# Ups_chg.net
KiCad netlist of a schematic drawn in Altium Designer
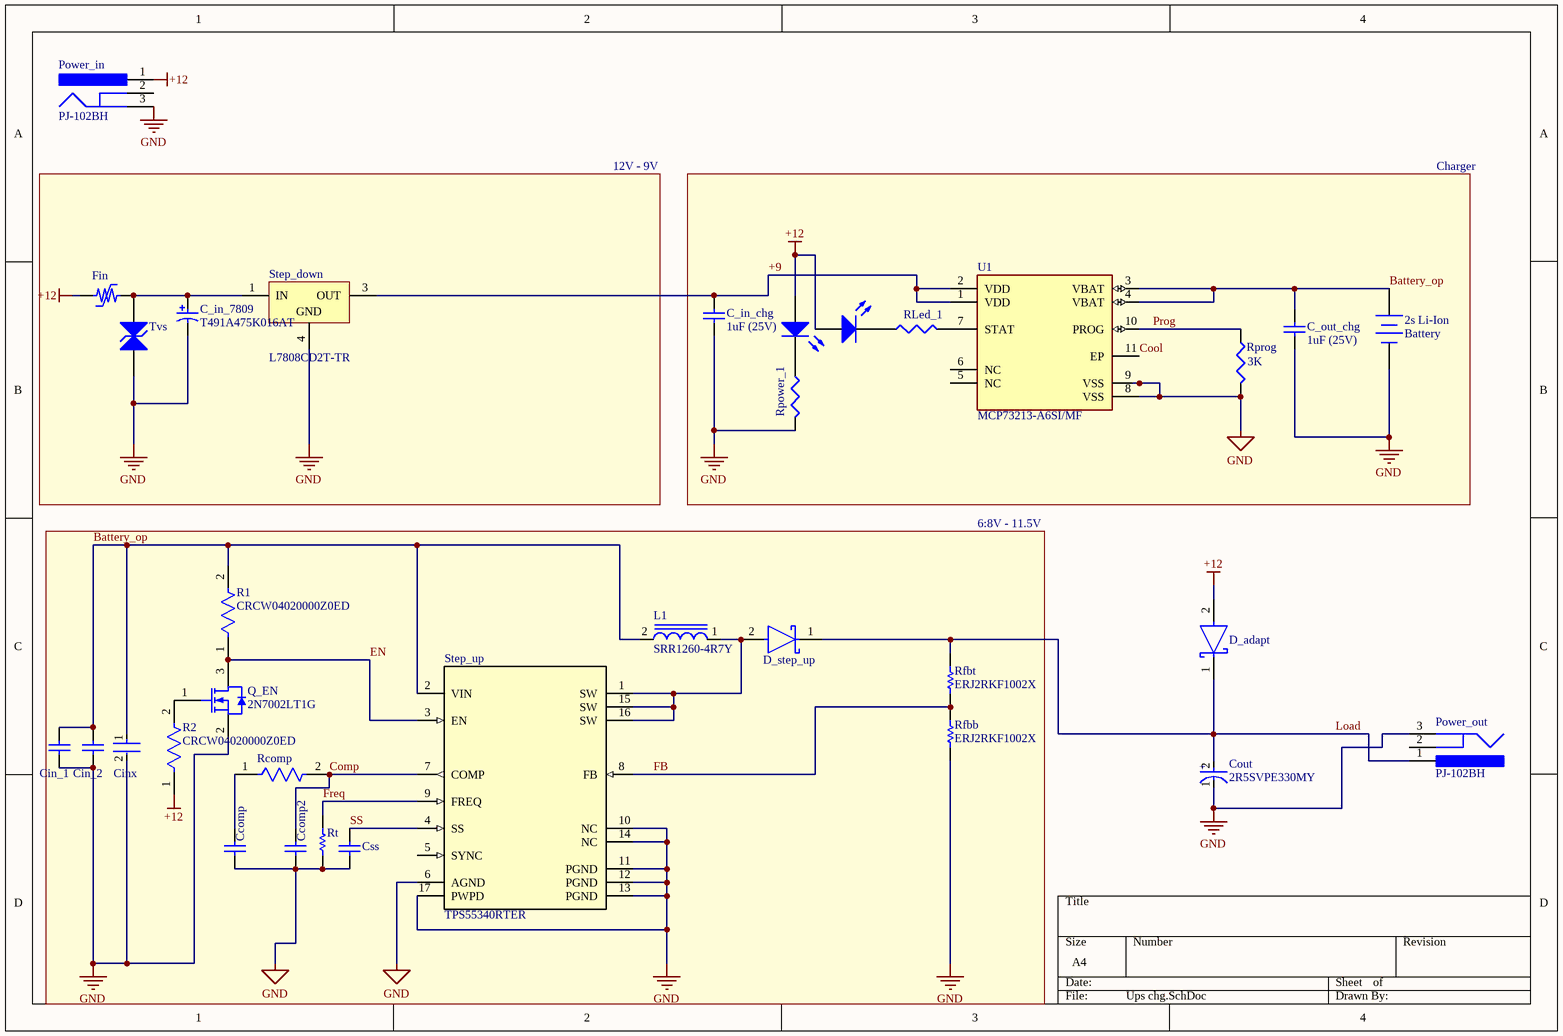
[diagram p0: Ups chg.SchDoc]

(export (version "E")
  (design (tool "Eeschema 10.0.6"))
  (components
    (comp (ref "2s Li-Ion")
      (value "Battery")
      (footprint "BAT-2")
      (description "Multicell Battery")
      (fields (field (name "PUBLISHER") "Altium Limited"))
      (libsource (lib "Miscellaneous Devices") (part "Battery"))
    )
    (comp (ref "Ccomp")
      (value "06035C102KAT2A")
      (footprint "CAPC1608X90X35LL15T15")
      (fields (field (name "MANUFACTURER") "AVX Interconnect / Elco"))
      (libsource (lib "Altium Content Vault") (part "CAP"))
    )
    (comp (ref "Ccomp2")
      (value "06035C102KAT2A")
      (footprint "CAPC1608X90X35LL15T15")
      (fields (field (name "MANUFACTURER") "AVX Interconnect / Elco"))
      (libsource (lib "Altium Content Vault") (part "CAP"))
    )
    (comp (ref "Cinx")
      (value "C0805C104M5RACTU")
      (footprint "FP-C0805C-DN-MFG")
      (description "CAP CER 0.1UF 50V X7R 0805")
      (fields
        (field (name "TOLERANCE") "0.2")
        (field (name "OCTOPART") "https://octopart.com/c0805c104m5ractu-kemet-129379")
      )
      (libsource (lib "Altium Content Vault") (part "b4654b650e69147ec39a6b967a45e02"))
    )
    (comp (ref "Cin_1")
      (value "C1206C106K4RACTU")
      (footprint "CAPC3216X180X50ML20T25")
      (description "CAP, Ceramic, 10 uF, +/- 10%, 16 V, -55 to 125 degC, 1206 (3216 Metric), RoHS, Tape and Reel")
      (fields (field (name "TOLERANCE") "5%"))
      (libsource (lib "Altium Content Vault") (part "CAP-NP-2"))
    )
    (comp (ref "Cin_2")
      (value "C1206C106K4RACTU")
      (footprint "CAPC3216X180X50ML20T25")
      (description "CAP, Ceramic, 10 uF, +/- 10%, 16 V, -55 to 125 degC, 1206 (3216 Metric), RoHS, Tape and Reel")
      (fields (field (name "TOLERANCE") "5%"))
      (libsource (lib "Altium Content Vault") (part "CAP-NP-2"))
    )
    (comp (ref "Cout")
      (value "2R5SVPE330MY")
      (footprint "FP-SVPE-B6-MFG")
      (description "CAP ALUM POLY 330UF 20% 2.5V SMD")
      (fields
        (field (name "OCTOPART") "https://octopart.com/2r5svpe330my-panasonic-29498404")
        (field (name "TOLERANCE") "20%")
      )
      (libsource (lib "Altium Content Vault") (part "a00bbbee19879c290e62620ae7e47b1"))
    )
    (comp (ref "Css")
      (value "06035C102KAT2A")
      (footprint "CAPC1608X90X35LL15T15")
      (fields (field (name "MANUFACTURER") "AVX Interconnect / Elco"))
      (libsource (lib "Altium Content Vault") (part "CAP"))
    )
    (comp (ref "C_in_7809")
      (value "T491A475K016AT")
      (footprint "KEMT-A-3216-18-2_L")
      (description "Tantalum Capacitor, 4.7 uF, +/- 10%, 16 V, -55 to 125 degC, 2-Pin Molded, RoHS, Tape and Reel")
      (fields (field (name "TOLERANCE") "10%") (field (name "MANUFACTURER") "Kemet"))
      (libsource (lib "Altium Content Vault") (part "CAP-P-2"))
    )
    (comp (ref "C_in_chg")
      (value "1uF (25V)")
      (footprint "CAPC2013X140X50LL20T25")
      (fields (field (name "PART NUMBER") "C0805C105K3RACTU") (field (name "MANUFACTURER") "Kemet"))
      (libsource (lib "Altium Content Vault") (part "CAP"))
    )
    (comp (ref "C_out_chg")
      (value "1uF (25V)")
      (footprint "CAPC2013X140X50LL20T25")
      (fields (field (name "PART NUMBER") "C0805C105K3RACTU") (field (name "MANUFACTURER") "Kemet"))
      (libsource (lib "Altium Content Vault") (part "CAP"))
    )
    (comp (ref "D_adapt")
      (value "B540C-13-F")
      (footprint "FP-SMC-MFG")
      (description "DIODE SCHOTTKY 40V 5A SMC")
      (fields
        (field (name "OCTOPART") "https://octopart.com/b540c-13-f-diodes+inc.-325873")
        (field (name "MANUFACTURER") "Diodes Inc.")
      )
      (libsource (lib "Altium Content Vault") (part "1d6ec82d83fb6aee721767c19dac4b9"))
    )
    (comp (ref "D_chg")
      (value "LED1")
      (footprint "LED-1")
      (description "Typical RED GaAs LED")
      (fields (field (name "PUBLISHER") "Altium Limited"))
      (libsource (lib "Miscellaneous Devices") (part "LED1"))
    )
    (comp (ref "D_step_up")
      (value "B540C-13-F")
      (footprint "FP-SMC-MFG")
      (description "DIODE SCHOTTKY 40V 5A SMC")
      (fields
        (field (name "OCTOPART") "https://octopart.com/b540c-13-f-diodes+inc.-325873")
        (field (name "MANUFACTURER") "Diodes Inc.")
      )
      (libsource (lib "Altium Content Vault") (part "1d6ec82d83fb6aee721767c19dac4b9"))
    )
    (comp (ref "Fin")
      (value "MF-MSMF075-2")
      (footprint "BOUR-MF-MSMF050-2_V")
      (description "PTC Resettable Fuse, 13.2 V, 750 mA, -40 to 85 degC, 2-Pin SMD, RoHS, Tape and Reel")
      (fields (field (name "MANUFACTURER") "Bourns"))
      (libsource (lib "Altium Content Vault") (part "PPTC-2"))
    )
    (comp (ref "L1")
      (value "SRR1260-4R7Y")
      (footprint "INDP125125X600N")
      (description "4.7ÂµH Shielded Wirewound Inductor 6.8A 15.5mOhm Max Nonstandard")
      (fields (field (name "MF") "Bourns"))
      (libsource (lib "SRR1260-4R7Y (1)") (part "SRR1260-4R7Y"))
    )
    (comp (ref "Power Good")
      (value "LED1")
      (footprint "LED-1")
      (description "Typical RED GaAs LED")
      (fields (field (name "PUBLISHER") "Altium Limited"))
      (libsource (lib "Miscellaneous Devices") (part "LED1"))
    )
    (comp (ref "Power_in")
      (value "PJ-102BH")
      (footprint "CUI-PJ-102BH_V")
      (fields (field (name "MANUFACTURER") "CUIInc."))
      (libsource (lib "Altium Content Vault") (part "JACK-2CD3-RN"))
    )
    (comp (ref "Power_out")
      (value "PJ-102BH")
      (footprint "CUI-PJ-102BH_V")
      (fields (field (name "MANUFACTURER") "CUIInc."))
      (libsource (lib "") (part "JACK-2CD3-RN_1"))
    )
    (comp (ref "Q_EN")
      (value "2N7002LT1G")
      (footprint "ONSC-SOT-23-3-318-08_V")
      (description "Small Signal MOSFET, 60 V, 115 mA, N-Channel, 3-Pin SOT-23, Pb-Free, Tape and Reel")
      (fields (field (name "MANUFACTURER") "On Semiconductor"))
      (libsource (lib "Altium Content Vault") (part "ONSC-NMOS-G1S2D3-3"))
    )
    (comp (ref "R1")
      (value "CRCW04020000Z0ED")
      (footprint "FP-CRCW0402-e3-IPC_C")
      (description "RES Thick Film, 0Ω, 0.063W, 0402")
      (fields (field (name "TOLERANCE") "5%"))
      (libsource (lib "Altium Content Vault") (part "1029c3af85768c4190bb7ad29bc67b5"))
    )
    (comp (ref "R2")
      (value "CRCW04020000Z0ED")
      (footprint "FP-CRCW0402-e3-IPC_C")
      (description "RES Thick Film, 0Ω, 0.063W, 0402")
      (fields (field (name "TOLERANCE") "5%"))
      (libsource (lib "Altium Content Vault") (part "1029c3af85768c4190bb7ad29bc67b5"))
    )
    (comp (ref "Rcomp")
      (value "CRCW04020000Z0ED")
      (footprint "FP-CRCW0402-e3-IPC_C")
      (description "RES Thick Film, 0Ω, 0.063W, 0402")
      (fields (field (name "TOLERANCE") "5%"))
      (libsource (lib "Altium Content Vault") (part "1029c3af85768c4190bb7ad29bc67b5"))
    )
    (comp (ref "Rfbb")
      (value "ERJ2RKF1002X")
      (footprint "RESC1005X40X25LL05T05")
      (description "Chip Resistor, 10 KOhm, +/- 1%, 0.1 W, -55 to 155 degC, 0402 (1005 Metric), RoHS, Tape and Reel")
      (fields (field (name "TOLERANCE") "1%") (field (name "MANUFACTURER") "Panasonic"))
      (libsource (lib "Altium Content Vault") (part "RES-2"))
    )
    (comp (ref "Rfbt")
      (value "ERJ2RKF1002X")
      (footprint "RESC1005X40X25LL05T05")
      (description "Chip Resistor, 10 KOhm, +/- 1%, 0.1 W, -55 to 155 degC, 0402 (1005 Metric), RoHS, Tape and Reel")
      (fields (field (name "TOLERANCE") "1%") (field (name "MANUFACTURER") "Panasonic"))
      (libsource (lib "Altium Content Vault") (part "RES-2"))
    )
    (comp (ref "RLed_1")
      (value "1K")
      (footprint "J1-0603")
      (description "Resistor")
      (fields (field (name "PUBLISHER") "Altium Limited"))
      (libsource (lib "Miscellaneous Devices") (part "Res3"))
    )
    (comp (ref "Rpower_1")
      (value "1K")
      (footprint "J1-0603")
      (description "Resistor")
      (fields (field (name "PUBLISHER") "Altium Limited"))
      (libsource (lib "Miscellaneous Devices") (part "Res3"))
    )
    (comp (ref "Rprog")
      (value "3K")
      (footprint "J1-0603")
      (description "Resistor")
      (fields (field (name "PUBLISHER") "Altium Limited"))
      (libsource (lib "Miscellaneous Devices") (part "Res3"))
    )
    (comp (ref "Rt")
      (value "CRCW08050000Z0EA")
      (footprint "RESC2013X50X30LL20T20")
      (fields (field (name "MANUFACTURER") "Vishay Dale"))
      (libsource (lib "Altium Content Vault") (part "RES"))
    )
    (comp (ref "Step_down")
      (value "L7808CD2T-TR")
      (footprint "TO-263_N")
      (description "Positive Voltage Regulator, 3-Pin D2PAK, Tape and Reel")
      (libsource (lib "Altium Content Vault") (part "PM-REG-L4940-SOT3"))
    )
    (comp (ref "Step_up")
      (value "TPS55340RTER")
      (footprint "RTE0016C")
      (description "No Description Available")
      (fields
        (field (name "MANUFACTURER") "Texas Instruments")
        (field (name "COPYRIGHT") "Copyright (C) 2018 Accelerated Designs. All rights reserved")
      )
      (libsource (lib "TPS55340") (part "TPS55340RTER"))
    )
    (comp (ref "Tvs")
      (value "SMAJ14CA-E3/61")
      (footprint "VISH-DO-214AC-2_N")
      (fields (field (name "MANUFACTURER") "Vishay Semiconductor"))
      (libsource (lib "Altium Content Vault") (part "VISH-A1A2-2"))
    )
    (comp (ref "U1")
      (value "MCP73213-A6SI/MF")
      (footprint "FP-C04-063-MFG")
      (description "IC LI-ION/LI-POLY CTRLR 10-DFN")
      (libsource (lib "Altium Content Vault") (part "4d2561e54ea19cff73a31b05b9c0e01"))
    )
  )
  (nets
    (net (code "1") (name "+12") (class "Default")
      (node (ref "D_adapt") (pin "2") (pinfunction "A_2") (pintype "passive"))
      (node (ref "D_chg") (pin "1") (pinfunction "A_1") (pintype "passive"))
      (node (ref "Fin") (pin "1") (pinfunction "1_1") (pintype "passive"))
      (node (ref "Power Good") (pin "1") (pinfunction "A_1") (pintype "passive"))
      (node (ref "Power_in") (pin "1") (pinfunction "1_1") (pintype "passive"))
      (node (ref "R2") (pin "1") (pinfunction "1_1") (pintype "passive"))
    )
    (net (code "2") (name "/+9") (class "Default")
      (node (ref "C_in_chg") (pin "2") (pinfunction "2_2") (pintype "passive"))
      (node (ref "Step_down") (pin "3") (pinfunction "OUT_3") (pintype "power_in"))
      (node (ref "U1") (pin "1") (pinfunction "VDD_1") (pintype "passive"))
      (node (ref "U1") (pin "2") (pinfunction "VDD_2") (pintype "passive"))
    )
    (net (code "3") (name "/Battery_op") (class "Default")
      (node (ref "2s Li-Ion") (pin "1") (pinfunction "+_1") (pintype "passive"))
      (node (ref "C_out_chg") (pin "2") (pinfunction "2_2") (pintype "passive"))
      (node (ref "Cin_1") (pin "2") (pinfunction "2_2") (pintype "passive"))
      (node (ref "Cin_2") (pin "2") (pinfunction "2_2") (pintype "passive"))
      (node (ref "Cinx") (pin "1") (pinfunction "1_1") (pintype "passive"))
      (node (ref "L1") (pin "2") (pinfunction "2_2") (pintype "passive"))
      (node (ref "R1") (pin "2") (pinfunction "2_2") (pintype "passive"))
      (node (ref "Step_up") (pin "2") (pinfunction "VIN_2") (pintype "power_in"))
      (node (ref "U1") (pin "3") (pinfunction "VBAT_3") (pintype "bidirectional"))
      (node (ref "U1") (pin "4") (pinfunction "VBAT_4") (pintype "bidirectional"))
    )
    (net (code "4") (name "/Comp") (class "Default")
      (node (ref "Ccomp2") (pin "2") (pinfunction "2_2") (pintype "passive"))
      (node (ref "Rcomp") (pin "2") (pinfunction "2_2") (pintype "passive"))
      (node (ref "Step_up") (pin "7") (pinfunction "COMP_7") (pintype "output"))
    )
    (net (code "5") (name "/Cool") (class "Default")
      (node (ref "U1") (pin "11") (pinfunction "EP_11") (pintype "power_in"))
    )
    (net (code "6") (name "/EN") (class "Default")
      (node (ref "Q_EN") (pin "3") (pinfunction "D_3") (pintype "passive"))
      (node (ref "R1") (pin "1") (pinfunction "1_1") (pintype "passive"))
      (node (ref "Step_up") (pin "3") (pinfunction "EN_3") (pintype "input"))
    )
    (net (code "7") (name "/FB") (class "Default")
      (node (ref "Rfbb") (pin "2") (pinfunction "2_2") (pintype "passive"))
      (node (ref "Rfbt") (pin "1") (pinfunction "1_1") (pintype "passive"))
      (node (ref "Step_up") (pin "8") (pinfunction "FB_8") (pintype "input"))
    )
    (net (code "8") (name "/Freq") (class "Default")
      (node (ref "Rt") (pin "2") (pinfunction "2_2") (pintype "passive"))
      (node (ref "Step_up") (pin "9") (pinfunction "FREQ_9") (pintype "input"))
    )
    (net (code "9") (name "/Load") (class "Default")
      (node (ref "Cout") (pin "2") (pinfunction "A_2") (pintype "passive"))
      (node (ref "D_adapt") (pin "1") (pinfunction "C_1") (pintype "passive"))
      (node (ref "D_step_up") (pin "1") (pinfunction "C_1") (pintype "passive"))
      (node (ref "Power_out") (pin "1") (pinfunction "1_1") (pintype "passive"))
      (node (ref "Rfbt") (pin "2") (pinfunction "2_2") (pintype "passive"))
    )
    (net (code "10") (name "/Prog") (class "Default")
      (node (ref "Rprog") (pin "1") (pinfunction "1_1") (pintype "passive"))
      (node (ref "U1") (pin "10") (pinfunction "PROG_10") (pintype "bidirectional"))
    )
    (net (code "11") (name "/SS") (class "Default")
      (node (ref "Css") (pin "2") (pinfunction "2_2") (pintype "passive"))
      (node (ref "Step_up") (pin "4") (pinfunction "SS_4") (pintype "input"))
    )
    (net (code "12") (name "GND") (class "Default")
      (node (ref "2s Li-Ion") (pin "2") (pinfunction "-_2") (pintype "passive"))
      (node (ref "C_in_7809") (pin "2") (pinfunction "2_2") (pintype "passive"))
      (node (ref "C_in_chg") (pin "1") (pinfunction "1_1") (pintype "passive"))
      (node (ref "C_out_chg") (pin "1") (pinfunction "1_1") (pintype "passive"))
      (node (ref "Ccomp") (pin "1") (pinfunction "1_1") (pintype "passive"))
      (node (ref "Ccomp2") (pin "1") (pinfunction "1_1") (pintype "passive"))
      (node (ref "Cin_1") (pin "1") (pinfunction "1_1") (pintype "passive"))
      (node (ref "Cin_2") (pin "1") (pinfunction "1_1") (pintype "passive"))
      (node (ref "Cinx") (pin "2") (pinfunction "2_2") (pintype "passive"))
      (node (ref "Cout") (pin "1") (pinfunction "C_1") (pintype "passive"))
      (node (ref "Css") (pin "1") (pinfunction "1_1") (pintype "passive"))
      (node (ref "Power_in") (pin "3") (pinfunction "3_3") (pintype "passive"))
      (node (ref "Power_out") (pin "3") (pinfunction "3_3") (pintype "passive"))
      (node (ref "Q_EN") (pin "2") (pinfunction "S_2") (pintype "passive"))
      (node (ref "Rfbb") (pin "1") (pinfunction "1_1") (pintype "passive"))
      (node (ref "Rpower_1") (pin "2") (pinfunction "2_2") (pintype "passive"))
      (node (ref "Rprog") (pin "2") (pinfunction "2_2") (pintype "passive"))
      (node (ref "Rt") (pin "1") (pinfunction "1_1") (pintype "passive"))
      (node (ref "Step_down") (pin "4") (pinfunction "GND_4") (pintype "power_in"))
      (node (ref "Step_up") (pin "10") (pinfunction "NC_10") (pintype "passive"))
      (node (ref "Step_up") (pin "11") (pinfunction "PGND_11") (pintype "power_in"))
      (node (ref "Step_up") (pin "12") (pinfunction "PGND_12") (pintype "power_in"))
      (node (ref "Step_up") (pin "13") (pinfunction "PGND_13") (pintype "power_in"))
      (node (ref "Step_up") (pin "14") (pinfunction "NC_14") (pintype "passive"))
      (node (ref "Step_up") (pin "17") (pinfunction "PWPD_17") (pintype "power_in"))
      (node (ref "Step_up") (pin "6") (pinfunction "AGND_6") (pintype "power_in"))
      (node (ref "Tvs") (pin "1") (pinfunction "A1_1") (pintype "passive"))
      (node (ref "U1") (pin "8") (pinfunction "VSS_8") (pintype "passive"))
      (node (ref "U1") (pin "9") (pinfunction "VSS_9") (pintype "passive"))
    )
    (net (code "13") (name "Net-(Ccomp-Pad2)") (class "Default")
      (node (ref "Ccomp") (pin "2") (pinfunction "2_2") (pintype "passive"))
      (node (ref "Rcomp") (pin "1") (pinfunction "1_1") (pintype "passive"))
    )
    (net (code "14") (name "Net-(D_chg-K)") (class "Default")
      (node (ref "D_chg") (pin "2") (pinfunction "K_2") (pintype "passive"))
      (node (ref "RLed_1") (pin "1") (pinfunction "1_1") (pintype "passive"))
    )
    (net (code "15") (name "Net-(D_step_up-A)") (class "Default")
      (node (ref "D_step_up") (pin "2") (pinfunction "A_2") (pintype "passive"))
      (node (ref "L1") (pin "1") (pinfunction "1_1") (pintype "passive"))
      (node (ref "Step_up") (pin "1") (pinfunction "SW_1") (pintype "power_in"))
      (node (ref "Step_up") (pin "15") (pinfunction "SW_15") (pintype "power_in"))
      (node (ref "Step_up") (pin "16") (pinfunction "SW_16") (pintype "power_in"))
    )
    (net (code "16") (name "Net-(Power Good-K)") (class "Default")
      (node (ref "Power Good") (pin "2") (pinfunction "K_2") (pintype "passive"))
      (node (ref "Rpower_1") (pin "1") (pinfunction "1_1") (pintype "passive"))
    )
    (net (code "17") (name "Net-(Q_EN-G)") (class "Default")
      (node (ref "Q_EN") (pin "1") (pinfunction "G_1") (pintype "passive"))
      (node (ref "R2") (pin "2") (pinfunction "2_2") (pintype "passive"))
    )
    (net (code "18") (name "Net-(Step_down-IN)") (class "Default")
      (node (ref "C_in_7809") (pin "1") (pinfunction "1_1") (pintype "passive"))
      (node (ref "Fin") (pin "2") (pinfunction "2_2") (pintype "passive"))
      (node (ref "Step_down") (pin "1") (pinfunction "IN_1") (pintype "power_in"))
      (node (ref "Tvs") (pin "2") (pinfunction "A2_2") (pintype "passive"))
    )
    (net (code "19") (name "Net-(U1-STAT)") (class "Default")
      (node (ref "RLed_1") (pin "2") (pinfunction "2_2") (pintype "passive"))
      (node (ref "U1") (pin "7") (pinfunction "STAT_7") (pintype "passive"))
    )
    (net (code "20") (name "unconnected-(Power_in-Pad2)") (class "Default")
      (node (ref "Power_in") (pin "2") (pinfunction "2_2") (pintype "passive"))
    )
    (net (code "21") (name "unconnected-(Power_out-Pad2)") (class "Default")
      (node (ref "Power_out") (pin "2") (pinfunction "2_2") (pintype "passive"))
    )
    (net (code "22") (name "unconnected-(Step_up-SYNC-Pad5)") (class "Default")
      (node (ref "Step_up") (pin "5") (pinfunction "SYNC_5") (pintype "input"))
    )
    (net (code "23") (name "unconnected-(U1-NC-Pad5)") (class "Default")
      (node (ref "U1") (pin "5") (pinfunction "NC_5") (pintype "passive"))
    )
    (net (code "24") (name "unconnected-(U1-NC-Pad6)") (class "Default")
      (node (ref "U1") (pin "6") (pinfunction "NC_6") (pintype "passive"))
    )
  )
)
